# Zio_9DOF_IMU_BNO080.net
KiCad netlist of a schematic drawn in EAGLE
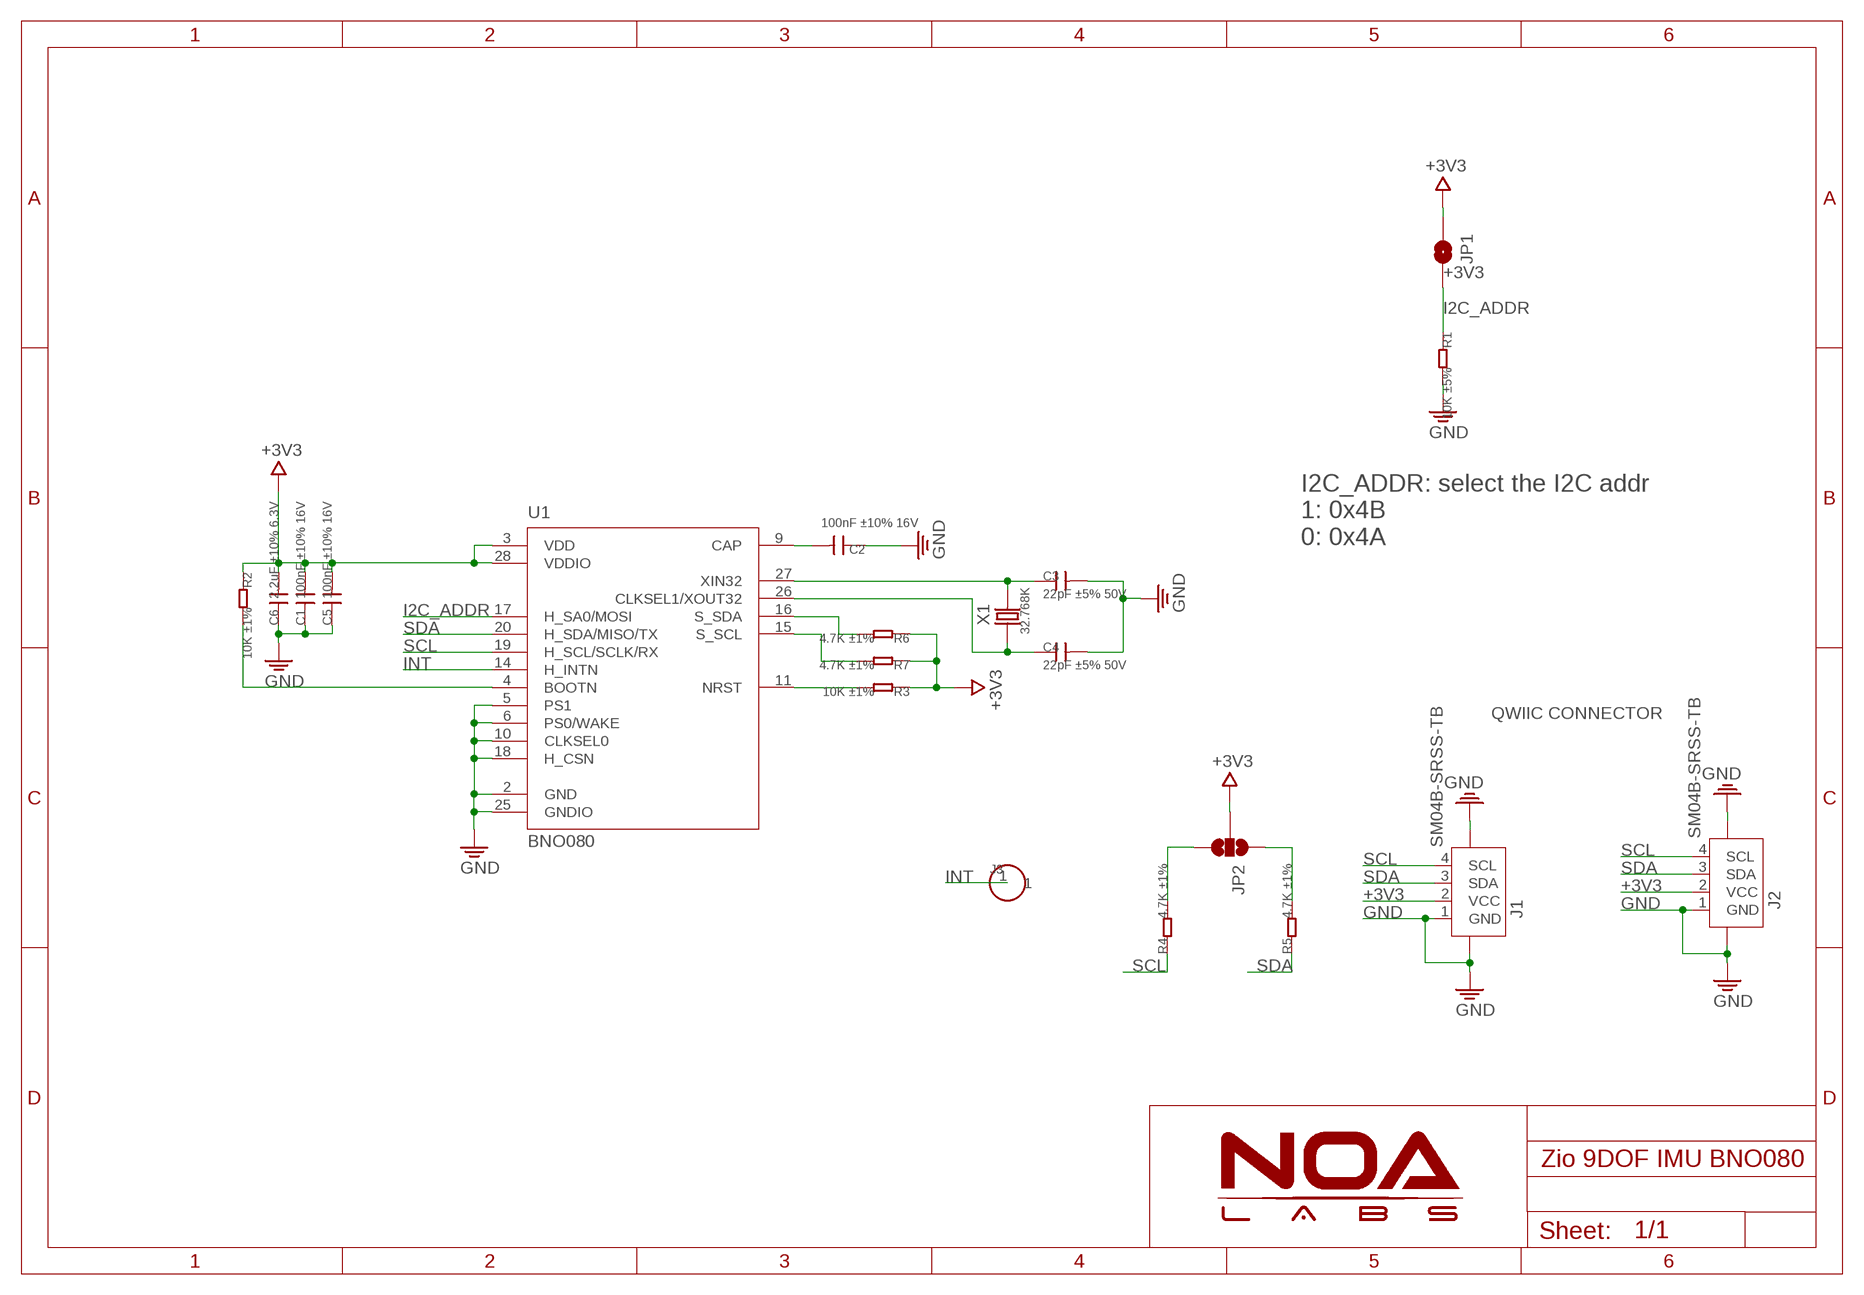
[diagram p0: schematic, sheet 1]

(export (version "E")
  (design (tool "Eeschema 10.0.6"))
  (components
    (comp (ref "C1")
      (value "100nF ±10% 16V")
      (footprint "eagle-import:0402")
      (libsource (lib "eagle-import") (part "C-0402"))
    )
    (comp (ref "C2")
      (value "100nF ±10% 16V")
      (footprint "eagle-import:0402")
      (libsource (lib "eagle-import") (part "C-0402"))
    )
    (comp (ref "C3")
      (value "22pF ±5% 50V")
      (footprint "eagle-import:0402")
      (libsource (lib "eagle-import") (part "C-0402"))
    )
    (comp (ref "C4")
      (value "22pF ±5% 50V")
      (footprint "eagle-import:0402")
      (libsource (lib "eagle-import") (part "C-0402"))
    )
    (comp (ref "C5")
      (value "100nF ±10% 16V")
      (footprint "eagle-import:0402")
      (libsource (lib "eagle-import") (part "C-0402"))
    )
    (comp (ref "C6")
      (value "2.2uF ±10% 6.3V")
      (footprint "eagle-import:0402")
      (libsource (lib "eagle-import") (part "C-0402"))
    )
    (comp (ref "J1")
      (value "SM04B-SRSS-TB")
      (footprint "eagle-import:JST-SH-4P")
      (libsource (lib "eagle-import") (part "JST-SH-4P-1.0"))
    )
    (comp (ref "J2")
      (value "SM04B-SRSS-TB")
      (footprint "eagle-import:JST-SH-4P")
      (libsource (lib "eagle-import") (part "JST-SH-4P-1.0"))
    )
    (comp (ref "J3")
      (value "HEADER-1P-40MIL")
      (footprint "eagle-import:1P-40MIL-AUTO")
      (libsource (lib "eagle-import") (part "HEADER-1P-40MIL"))
    )
    (comp (ref "JP1")
      (value "JUMPER-SMT_2_NO_SILK")
      (footprint "eagle-import:SMT-JUMPER_2_NO_SILK")
      (libsource (lib "eagle-import") (part "JUMPER-SMT_2_NO_SILK"))
    )
    (comp (ref "JP2")
      (value "JUMPER-SMT_3_2-NC_PASTE_NOCREM")
      (footprint "eagle-import:SMT-JUMPER_3_2-NC_PASTE_SILK_NOCREM")
      (libsource (lib "eagle-import") (part "JUMPER-SMT_3_2-NC_PASTE_NOCREM"))
    )
    (comp (ref "R1")
      (value "10K ±5%")
      (footprint "eagle-import:0402")
      (libsource (lib "eagle-import") (part "R-0402"))
    )
    (comp (ref "R2")
      (value "10K ±1%")
      (footprint "eagle-import:0402")
      (libsource (lib "eagle-import") (part "R-0402"))
    )
    (comp (ref "R3")
      (value "10K ±1%")
      (footprint "eagle-import:0402")
      (libsource (lib "eagle-import") (part "R-0402"))
    )
    (comp (ref "R4")
      (value "4.7K ±1%")
      (footprint "eagle-import:0402")
      (libsource (lib "eagle-import") (part "Discretex_R-0402"))
    )
    (comp (ref "R5")
      (value "4.7K ±1%")
      (footprint "eagle-import:0402")
      (libsource (lib "eagle-import") (part "Discretex_R-0402"))
    )
    (comp (ref "R6")
      (value "4.7K ±1%")
      (footprint "eagle-import:0402")
      (libsource (lib "eagle-import") (part "Discretex_R-0402"))
    )
    (comp (ref "R7")
      (value "4.7K ±1%")
      (footprint "eagle-import:0402")
      (libsource (lib "eagle-import") (part "Discretex_R-0402"))
    )
    (comp (ref "U1")
      (value "BNO080")
      (footprint "eagle-import:IC_LGA-28_3.80X5.20_0.5")
      (libsource (lib "eagle-import") (part "BNO080"))
    )
    (comp (ref "X1")
      (value "32.768K")
      (footprint "eagle-import:2.0X12MM")
      (libsource (lib "eagle-import") (part "CRYSTAL-2012"))
    )
  )
  (nets
    (net (code "1") (name "+3V3") (class "Default")
      (node (ref "C1") (pin "2") (pinfunction "2_2") (pintype "passive"))
      (node (ref "C5") (pin "2") (pinfunction "2_2") (pintype "passive"))
      (node (ref "C6") (pin "2") (pinfunction "2_2") (pintype "passive"))
      (node (ref "J1") (pin "2") (pinfunction "VCC_2") (pintype "bidirectional"))
      (node (ref "J2") (pin "2") (pinfunction "VCC_2") (pintype "bidirectional"))
      (node (ref "JP1") (pin "1") (pinfunction "1_1") (pintype "passive"))
      (node (ref "JP2") (pin "2") (pinfunction "2_2") (pintype "passive"))
      (node (ref "R2") (pin "1") (pinfunction "1_1") (pintype "passive"))
      (node (ref "R3") (pin "1") (pinfunction "1_1") (pintype "passive"))
      (node (ref "R6") (pin "1") (pinfunction "1_1") (pintype "passive"))
      (node (ref "R7") (pin "1") (pinfunction "1_1") (pintype "passive"))
      (node (ref "U1") (pin "28") (pinfunction "VDDIO_28") (pintype "bidirectional"))
      (node (ref "U1") (pin "3") (pinfunction "VDD_3") (pintype "bidirectional"))
    )
    (net (code "2") (name "/I2C_ADDR") (class "Default")
      (node (ref "JP1") (pin "2") (pinfunction "2_2") (pintype "passive"))
      (node (ref "R1") (pin "1") (pinfunction "1_1") (pintype "passive"))
      (node (ref "U1") (pin "17") (pinfunction "H_SA0/MOSI_17") (pintype "bidirectional"))
    )
    (net (code "3") (name "/INT") (class "Default")
      (node (ref "J3") (pin "1") (pinfunction "1_1") (pintype "bidirectional"))
      (node (ref "U1") (pin "14") (pinfunction "H_INTN_14") (pintype "bidirectional"))
    )
    (net (code "4") (name "/SCL") (class "Default")
      (node (ref "J1") (pin "4") (pinfunction "SCL_4") (pintype "bidirectional"))
      (node (ref "J2") (pin "4") (pinfunction "SCL_4") (pintype "bidirectional"))
      (node (ref "R4") (pin "1") (pinfunction "1_1") (pintype "passive"))
      (node (ref "U1") (pin "19") (pinfunction "H_SCL/SCLK/RX_19") (pintype "bidirectional"))
    )
    (net (code "5") (name "/SDA") (class "Default")
      (node (ref "J1") (pin "3") (pinfunction "SDA_3") (pintype "bidirectional"))
      (node (ref "J2") (pin "3") (pinfunction "SDA_3") (pintype "bidirectional"))
      (node (ref "R5") (pin "1") (pinfunction "1_1") (pintype "passive"))
      (node (ref "U1") (pin "20") (pinfunction "H_SDA/MISO/TX_20") (pintype "bidirectional"))
    )
    (net (code "6") (name "GND") (class "Default")
      (node (ref "C1") (pin "1") (pinfunction "1_1") (pintype "passive"))
      (node (ref "C2") (pin "1") (pinfunction "1_1") (pintype "passive"))
      (node (ref "C3") (pin "2") (pinfunction "2_2") (pintype "passive"))
      (node (ref "C4") (pin "2") (pinfunction "2_2") (pintype "passive"))
      (node (ref "C5") (pin "1") (pinfunction "1_1") (pintype "passive"))
      (node (ref "C6") (pin "1") (pinfunction "1_1") (pintype "passive"))
      (node (ref "J1") (pin "1") (pinfunction "GND_1") (pintype "bidirectional"))
      (node (ref "J1") (pin "NC1") (pinfunction "5_NC1") (pintype "bidirectional"))
      (node (ref "J1") (pin "NC2") (pinfunction "6_NC2") (pintype "bidirectional"))
      (node (ref "J2") (pin "1") (pinfunction "GND_1") (pintype "bidirectional"))
      (node (ref "J2") (pin "NC1") (pinfunction "5_NC1") (pintype "bidirectional"))
      (node (ref "J2") (pin "NC2") (pinfunction "6_NC2") (pintype "bidirectional"))
      (node (ref "R1") (pin "2") (pinfunction "2_2") (pintype "passive"))
      (node (ref "U1") (pin "10") (pinfunction "CLKSEL0_10") (pintype "bidirectional"))
      (node (ref "U1") (pin "18") (pinfunction "H_CSN_18") (pintype "bidirectional"))
      (node (ref "U1") (pin "2") (pinfunction "GND_2") (pintype "bidirectional"))
      (node (ref "U1") (pin "25") (pinfunction "GNDIO_25") (pintype "bidirectional"))
      (node (ref "U1") (pin "5") (pinfunction "PS1_5") (pintype "bidirectional"))
      (node (ref "U1") (pin "6") (pinfunction "PS0/WAKE_6") (pintype "bidirectional"))
    )
    (net (code "7") (name "Net-(JP2-Pad1)") (class "Default")
      (node (ref "JP2") (pin "1") (pinfunction "1_1") (pintype "passive"))
      (node (ref "R5") (pin "2") (pinfunction "2_2") (pintype "passive"))
    )
    (net (code "8") (name "Net-(JP2-Pad3)") (class "Default")
      (node (ref "JP2") (pin "3") (pinfunction "3_3") (pintype "passive"))
      (node (ref "R4") (pin "2") (pinfunction "2_2") (pintype "passive"))
    )
    (net (code "9") (name "Net-(U1-BOOTN)") (class "Default")
      (node (ref "R2") (pin "2") (pinfunction "2_2") (pintype "passive"))
      (node (ref "U1") (pin "4") (pinfunction "BOOTN_4") (pintype "bidirectional"))
    )
    (net (code "10") (name "Net-(U1-CAP)") (class "Default")
      (node (ref "C2") (pin "2") (pinfunction "2_2") (pintype "passive"))
      (node (ref "U1") (pin "9") (pinfunction "CAP_9") (pintype "bidirectional"))
    )
    (net (code "11") (name "Net-(U1-CLKSEL1{slash}XOUT32)") (class "Default")
      (node (ref "C4") (pin "1") (pinfunction "1_1") (pintype "passive"))
      (node (ref "U1") (pin "26") (pinfunction "CLKSEL1/XOUT32_26") (pintype "bidirectional"))
      (node (ref "X1") (pin "1") (pinfunction "1_1") (pintype "passive"))
    )
    (net (code "12") (name "Net-(U1-NRST)") (class "Default")
      (node (ref "R3") (pin "2") (pinfunction "2_2") (pintype "passive"))
      (node (ref "U1") (pin "11") (pinfunction "NRST_11") (pintype "bidirectional"))
    )
    (net (code "13") (name "Net-(U1-S_SCL)") (class "Default")
      (node (ref "R7") (pin "2") (pinfunction "2_2") (pintype "passive"))
      (node (ref "U1") (pin "15") (pinfunction "S_SCL_15") (pintype "bidirectional"))
    )
    (net (code "14") (name "Net-(U1-S_SDA)") (class "Default")
      (node (ref "R6") (pin "2") (pinfunction "2_2") (pintype "passive"))
      (node (ref "U1") (pin "16") (pinfunction "S_SDA_16") (pintype "bidirectional"))
    )
    (net (code "15") (name "Net-(U1-XIN32)") (class "Default")
      (node (ref "C3") (pin "1") (pinfunction "1_1") (pintype "passive"))
      (node (ref "U1") (pin "27") (pinfunction "XIN32_27") (pintype "bidirectional"))
      (node (ref "X1") (pin "2") (pinfunction "2_2") (pintype "passive"))
    )
  )
)
